# recall_ble_mod_v0_1.net
KiCad netlist of a schematic drawn in Altium Designer
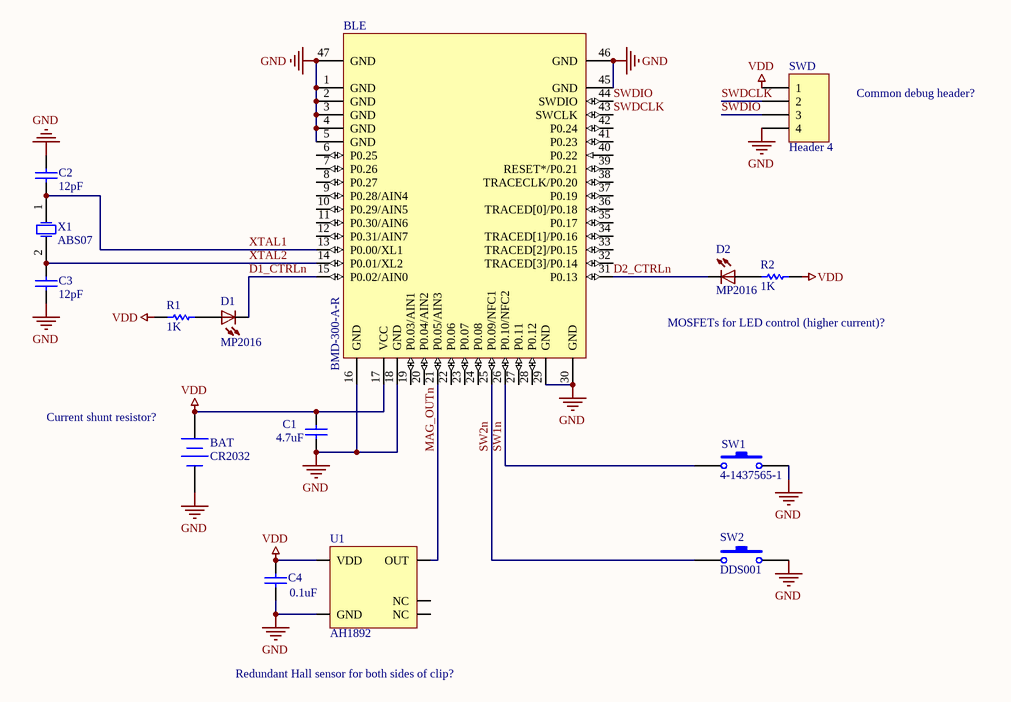
[diagram p0: recall_ble_mod_v0_1.SchDoc]

(export (version "E")
  (design (tool "Eeschema 10.0.6"))
  (components
    (comp (ref "BAT")
      (value "CR2032")
      (footprint "BAT-HLD-001-THM")
      (fields (field (name "PUBLISHER") "Altium Limited"))
      (libsource (lib "recall") (part "Battery"))
    )
    (comp (ref "BLE")
      (value "BMD-300")
      (footprint "BMD-300")
      (description "Bluetooth 4.2 LE Module, nRF52832, 512kB Flash, 64kB RAM")
      (fields
        (field (name "PART NUMBER") "BMD-300-A")
        (field (name "MANUFACTURER") "Rigado")
        (field (name "MANUFACTURER P/N") "BMD-300-A-R")
        (field (name "ADDED BY") "Cam N")
      )
      (libsource (lib "recall") (part "BMD-300-A"))
    )
    (comp (ref "C1")
      (value "4.7uF")
      (footprint "CAP_0603R")
      (description "Capacitor")
      (fields (field (name "Comment") "CAP") (field (name "PUBLISHER") "Altium Limited"))
      (libsource (lib "EllieGrid_v0_2") (part "CAP"))
    )
    (comp (ref "C2")
      (value "12pF")
      (footprint "CAP_0402R")
      (description "Capacitor")
      (fields (field (name "Comment") "CAP") (field (name "PUBLISHER") "Altium Limited"))
      (libsource (lib "EllieGrid_v0_2") (part "CAP"))
    )
    (comp (ref "C3")
      (value "12pF")
      (footprint "CAP_0402R")
      (description "Capacitor")
      (fields (field (name "Comment") "CAP") (field (name "PUBLISHER") "Altium Limited"))
      (libsource (lib "EllieGrid_v0_2") (part "CAP"))
    )
    (comp (ref "C4")
      (value "0.1uF")
      (footprint "CAP_0402R")
      (description "Capacitor")
      (fields (field (name "Comment") "CAP") (field (name "PUBLISHER") "Altium Limited"))
      (libsource (lib "recall") (part "CAP"))
    )
    (comp (ref "D1")
      (value "MP2016")
      (footprint "MP2016_centered")
      (description "MP2016 White LED")
      (libsource (lib "recall") (part "MP2016"))
    )
    (comp (ref "D2")
      (value "MP2016")
      (footprint "MP2016_centered")
      (description "MP2016 White LED")
      (libsource (lib "recall") (part "MP2016"))
    )
    (comp (ref "R1")
      (value "1K")
      (footprint "RES_0402")
      (description "Resistor")
      (fields (field (name "Comment") "RES") (field (name "PUBLISHER") "Altium Limited"))
      (libsource (lib "recall") (part "RES"))
    )
    (comp (ref "R2")
      (value "1K")
      (footprint "RES_0402")
      (description "Resistor")
      (fields (field (name "Comment") "RES") (field (name "PUBLISHER") "Altium Limited"))
      (libsource (lib "recall") (part "RES"))
    )
    (comp (ref "SW1")
      (value "4-1437565-1")
      (footprint "4-1437565-1")
      (description "Translucent Conductive Silicone Elastomer Switch")
      (fields (field (name "PUBLISHER") "Altium Limited"))
      (libsource (lib "recall") (part "SW-TACT"))
    )
    (comp (ref "SW2")
      (value "DDS001")
      (footprint "DDS001")
      (description "Translucent Conductive Silicone Elastomer Switch")
      (fields (field (name "PUBLISHER") "Altium Limited"))
      (libsource (lib "recall") (part "SW-PB"))
    )
    (comp (ref "SWD")
      (value "Header 4")
      (footprint "HDR1X4_SWD")
      (description "Header, 4-Pin")
      (fields (field (name "PUBLISHER") "Altium Limited"))
      (libsource (lib "recall") (part "Header 4"))
    )
    (comp (ref "U1")
      (value "AH1892")
      (footprint "sot-553")
      (description "Hall effect switch")
      (libsource (lib "recall") (part "AH1892"))
    )
    (comp (ref "X1")
      (value "ABS07")
      (footprint "ABS07")
      (description "ABS25")
      (libsource (lib "EllieGrid_v0_2") (part "ABS07"))
    )
  )
  (nets
    (net (code "1") (name "/D1_CTRLn") (class "Default")
      (node (ref "BLE") (pin "15") (pinfunction "P0.02/AIN0_15") (pintype "bidirectional"))
      (node (ref "D1") (pin "C") (pinfunction "C_C") (pintype "passive"))
    )
    (net (code "2") (name "/D2_CTRLn") (class "Default")
      (node (ref "BLE") (pin "31") (pinfunction "P0.13_31") (pintype "bidirectional"))
      (node (ref "D2") (pin "C") (pinfunction "C_C") (pintype "passive"))
    )
    (net (code "3") (name "/MAG_OUTn") (class "Default")
      (node (ref "BLE") (pin "21") (pinfunction "P0.05/AIN3_21") (pintype "bidirectional"))
      (node (ref "U1") (pin "5") (pinfunction "OUT_5") (pintype "passive"))
    )
    (net (code "4") (name "/SW1n") (class "Default")
      (node (ref "BLE") (pin "26") (pinfunction "P0.10/NFC2_26") (pintype "bidirectional"))
      (node (ref "SW1") (pin "1") (pinfunction "1_1") (pintype "passive"))
    )
    (net (code "5") (name "/SW2n") (class "Default")
      (node (ref "BLE") (pin "25") (pinfunction "P0.09/NFC1_25") (pintype "bidirectional"))
      (node (ref "SW2") (pin "1") (pinfunction "1_1") (pintype "passive"))
    )
    (net (code "6") (name "/SWDCLK") (class "Default")
      (node (ref "BLE") (pin "43") (pinfunction "SWCLK_43") (pintype "bidirectional"))
      (node (ref "SWD") (pin "2") (pinfunction "2_2") (pintype "passive"))
    )
    (net (code "7") (name "/SWDIO") (class "Default")
      (node (ref "BLE") (pin "44") (pinfunction "SWDIO_44") (pintype "bidirectional"))
      (node (ref "SWD") (pin "3") (pinfunction "3_3") (pintype "passive"))
    )
    (net (code "8") (name "/XTAL1") (class "Default")
      (node (ref "BLE") (pin "13") (pinfunction "P0.00/XL1_13") (pintype "bidirectional"))
      (node (ref "C2") (pin "2") (pinfunction "2_2") (pintype "passive"))
      (node (ref "X1") (pin "1") (pinfunction "OSC1_1") (pintype "passive"))
    )
    (net (code "9") (name "/XTAL2") (class "Default")
      (node (ref "BLE") (pin "14") (pinfunction "P0.01/XL2_14") (pintype "bidirectional"))
      (node (ref "C3") (pin "2") (pinfunction "2_2") (pintype "passive"))
      (node (ref "X1") (pin "2") (pinfunction "OSC2_2") (pintype "passive"))
    )
    (net (code "10") (name "GND") (class "Default")
      (node (ref "BAT") (pin "2") (pinfunction "-_2") (pintype "passive"))
      (node (ref "BLE") (pin "1") (pinfunction "GND_1") (pintype "power_in"))
      (node (ref "BLE") (pin "16") (pinfunction "GND_16") (pintype "power_in"))
      (node (ref "BLE") (pin "18") (pinfunction "GND_18") (pintype "power_in"))
      (node (ref "BLE") (pin "2") (pinfunction "GND_2") (pintype "power_in"))
      (node (ref "BLE") (pin "29") (pinfunction "GND_29") (pintype "power_in"))
      (node (ref "BLE") (pin "3") (pinfunction "GND_3") (pintype "power_in"))
      (node (ref "BLE") (pin "30") (pinfunction "GND_30") (pintype "power_in"))
      (node (ref "BLE") (pin "4") (pinfunction "GND_4") (pintype "power_in"))
      (node (ref "BLE") (pin "45") (pinfunction "GND_45") (pintype "power_in"))
      (node (ref "BLE") (pin "46") (pinfunction "GND_46") (pintype "power_in"))
      (node (ref "BLE") (pin "47") (pinfunction "GND_47") (pintype "power_in"))
      (node (ref "BLE") (pin "5") (pinfunction "GND_5") (pintype "power_in"))
      (node (ref "C1") (pin "1") (pinfunction "1_1") (pintype "passive"))
      (node (ref "C2") (pin "1") (pinfunction "1_1") (pintype "passive"))
      (node (ref "C3") (pin "1") (pinfunction "1_1") (pintype "passive"))
      (node (ref "C4") (pin "1") (pinfunction "1_1") (pintype "passive"))
      (node (ref "SW1") (pin "2") (pinfunction "2_2") (pintype "passive"))
      (node (ref "SW2") (pin "2") (pinfunction "2_2") (pintype "passive"))
      (node (ref "SWD") (pin "4") (pinfunction "4_4") (pintype "passive"))
      (node (ref "U1") (pin "4") (pinfunction "GND_4") (pintype "passive"))
    )
    (net (code "11") (name "Net-(D1-PadA)") (class "Default")
      (node (ref "D1") (pin "A") (pinfunction "A_A") (pintype "passive"))
      (node (ref "R1") (pin "2") (pinfunction "2_2") (pintype "passive"))
    )
    (net (code "12") (name "Net-(D2-PadA)") (class "Default")
      (node (ref "D2") (pin "A") (pinfunction "A_A") (pintype "passive"))
      (node (ref "R2") (pin "2") (pinfunction "2_2") (pintype "passive"))
    )
    (net (code "13") (name "VDD") (class "Default")
      (node (ref "BAT") (pin "1") (pinfunction "+_1") (pintype "passive"))
      (node (ref "BLE") (pin "17") (pinfunction "VCC_17") (pintype "power_in"))
      (node (ref "C1") (pin "2") (pinfunction "2_2") (pintype "passive"))
      (node (ref "C4") (pin "2") (pinfunction "2_2") (pintype "passive"))
      (node (ref "R1") (pin "1") (pinfunction "1_1") (pintype "passive"))
      (node (ref "R2") (pin "1") (pinfunction "1_1") (pintype "passive"))
      (node (ref "SWD") (pin "1") (pinfunction "1_1") (pintype "passive"))
      (node (ref "U1") (pin "1") (pinfunction "VDD_1") (pintype "passive"))
    )
    (net (code "14") (name "unconnected-(BLE-P0.03{slash}AIN1-Pad19)") (class "Default")
      (node (ref "BLE") (pin "19") (pinfunction "P0.03/AIN1_19") (pintype "bidirectional"))
    )
    (net (code "15") (name "unconnected-(BLE-P0.04{slash}AIN2-Pad20)") (class "Default")
      (node (ref "BLE") (pin "20") (pinfunction "P0.04/AIN2_20") (pintype "bidirectional"))
    )
    (net (code "16") (name "unconnected-(BLE-P0.06-Pad22)") (class "Default")
      (node (ref "BLE") (pin "22") (pinfunction "P0.06_22") (pintype "bidirectional"))
    )
    (net (code "17") (name "unconnected-(BLE-P0.07-Pad23)") (class "Default")
      (node (ref "BLE") (pin "23") (pinfunction "P0.07_23") (pintype "bidirectional"))
    )
    (net (code "18") (name "unconnected-(BLE-P0.08-Pad24)") (class "Default")
      (node (ref "BLE") (pin "24") (pinfunction "P0.08_24") (pintype "bidirectional"))
    )
    (net (code "19") (name "unconnected-(BLE-P0.11-Pad27)") (class "Default")
      (node (ref "BLE") (pin "27") (pinfunction "P0.11_27") (pintype "bidirectional"))
    )
    (net (code "20") (name "unconnected-(BLE-P0.12-Pad28)") (class "Default")
      (node (ref "BLE") (pin "28") (pinfunction "P0.12_28") (pintype "bidirectional"))
    )
    (net (code "21") (name "unconnected-(BLE-P0.17-Pad35)") (class "Default")
      (node (ref "BLE") (pin "35") (pinfunction "P0.17_35") (pintype "bidirectional"))
    )
    (net (code "22") (name "unconnected-(BLE-P0.19-Pad37)") (class "Default")
      (node (ref "BLE") (pin "37") (pinfunction "P0.19_37") (pintype "bidirectional"))
    )
    (net (code "23") (name "unconnected-(BLE-P0.22-Pad40)") (class "Default")
      (node (ref "BLE") (pin "40") (pinfunction "P0.22_40") (pintype "input"))
    )
    (net (code "24") (name "unconnected-(BLE-P0.23-Pad41)") (class "Default")
      (node (ref "BLE") (pin "41") (pinfunction "P0.23_41") (pintype "bidirectional"))
    )
    (net (code "25") (name "unconnected-(BLE-P0.24-Pad42)") (class "Default")
      (node (ref "BLE") (pin "42") (pinfunction "P0.24_42") (pintype "bidirectional"))
    )
    (net (code "26") (name "unconnected-(BLE-P0.25-Pad6)") (class "Default")
      (node (ref "BLE") (pin "6") (pinfunction "P0.25_6") (pintype "bidirectional"))
    )
    (net (code "27") (name "unconnected-(BLE-P0.26-Pad7)") (class "Default")
      (node (ref "BLE") (pin "7") (pinfunction "P0.26_7") (pintype "bidirectional"))
    )
    (net (code "28") (name "unconnected-(BLE-P0.27-Pad8)") (class "Default")
      (node (ref "BLE") (pin "8") (pinfunction "P0.27_8") (pintype "bidirectional"))
    )
    (net (code "29") (name "unconnected-(BLE-P0.28{slash}AIN4-Pad9)") (class "Default")
      (node (ref "BLE") (pin "9") (pinfunction "P0.28/AIN4_9") (pintype "bidirectional"))
    )
    (net (code "30") (name "unconnected-(BLE-P0.29{slash}AIN5-Pad10)") (class "Default")
      (node (ref "BLE") (pin "10") (pinfunction "P0.29/AIN5_10") (pintype "bidirectional"))
    )
    (net (code "31") (name "unconnected-(BLE-P0.30{slash}AIN6-Pad11)") (class "Default")
      (node (ref "BLE") (pin "11") (pinfunction "P0.30/AIN6_11") (pintype "bidirectional"))
    )
    (net (code "32") (name "unconnected-(BLE-P0.31{slash}AIN7-Pad12)") (class "Default")
      (node (ref "BLE") (pin "12") (pinfunction "P0.31/AIN7_12") (pintype "bidirectional"))
    )
    (net (code "33") (name "unconnected-(BLE-RESET*{slash}P0.21-Pad39)") (class "Default")
      (node (ref "BLE") (pin "39") (pinfunction "RESET*/P0.21_39") (pintype "bidirectional"))
    )
    (net (code "34") (name "unconnected-(BLE-TRACECLK{slash}P0.20-Pad38)") (class "Default")
      (node (ref "BLE") (pin "38") (pinfunction "TRACECLK/P0.20_38") (pintype "bidirectional"))
    )
    (net (code "35") (name "unconnected-(BLE-TRACED[0]{slash}P0.18-Pad36)") (class "Default")
      (node (ref "BLE") (pin "36") (pinfunction "TRACED[0]/P0.18_36") (pintype "bidirectional"))
    )
    (net (code "36") (name "unconnected-(BLE-TRACED[1]{slash}P0.16-Pad34)") (class "Default")
      (node (ref "BLE") (pin "34") (pinfunction "TRACED[1]/P0.16_34") (pintype "bidirectional"))
    )
    (net (code "37") (name "unconnected-(BLE-TRACED[2]{slash}P0.15-Pad33)") (class "Default")
      (node (ref "BLE") (pin "33") (pinfunction "TRACED[2]/P0.15_33") (pintype "bidirectional"))
    )
    (net (code "38") (name "unconnected-(BLE-TRACED[3]{slash}P0.14-Pad32)") (class "Default")
      (node (ref "BLE") (pin "32") (pinfunction "TRACED[3]/P0.14_32") (pintype "bidirectional"))
    )
    (net (code "39") (name "unconnected-(U1-NC-Pad2)") (class "Default")
      (node (ref "U1") (pin "2") (pinfunction "NC_2") (pintype "passive"))
    )
    (net (code "40") (name "unconnected-(U1-NC-Pad3)") (class "Default")
      (node (ref "U1") (pin "3") (pinfunction "NC_3") (pintype "passive"))
    )
  )
)
